# AC_board.net
KiCad netlist of a schematic drawn in Altium Designer
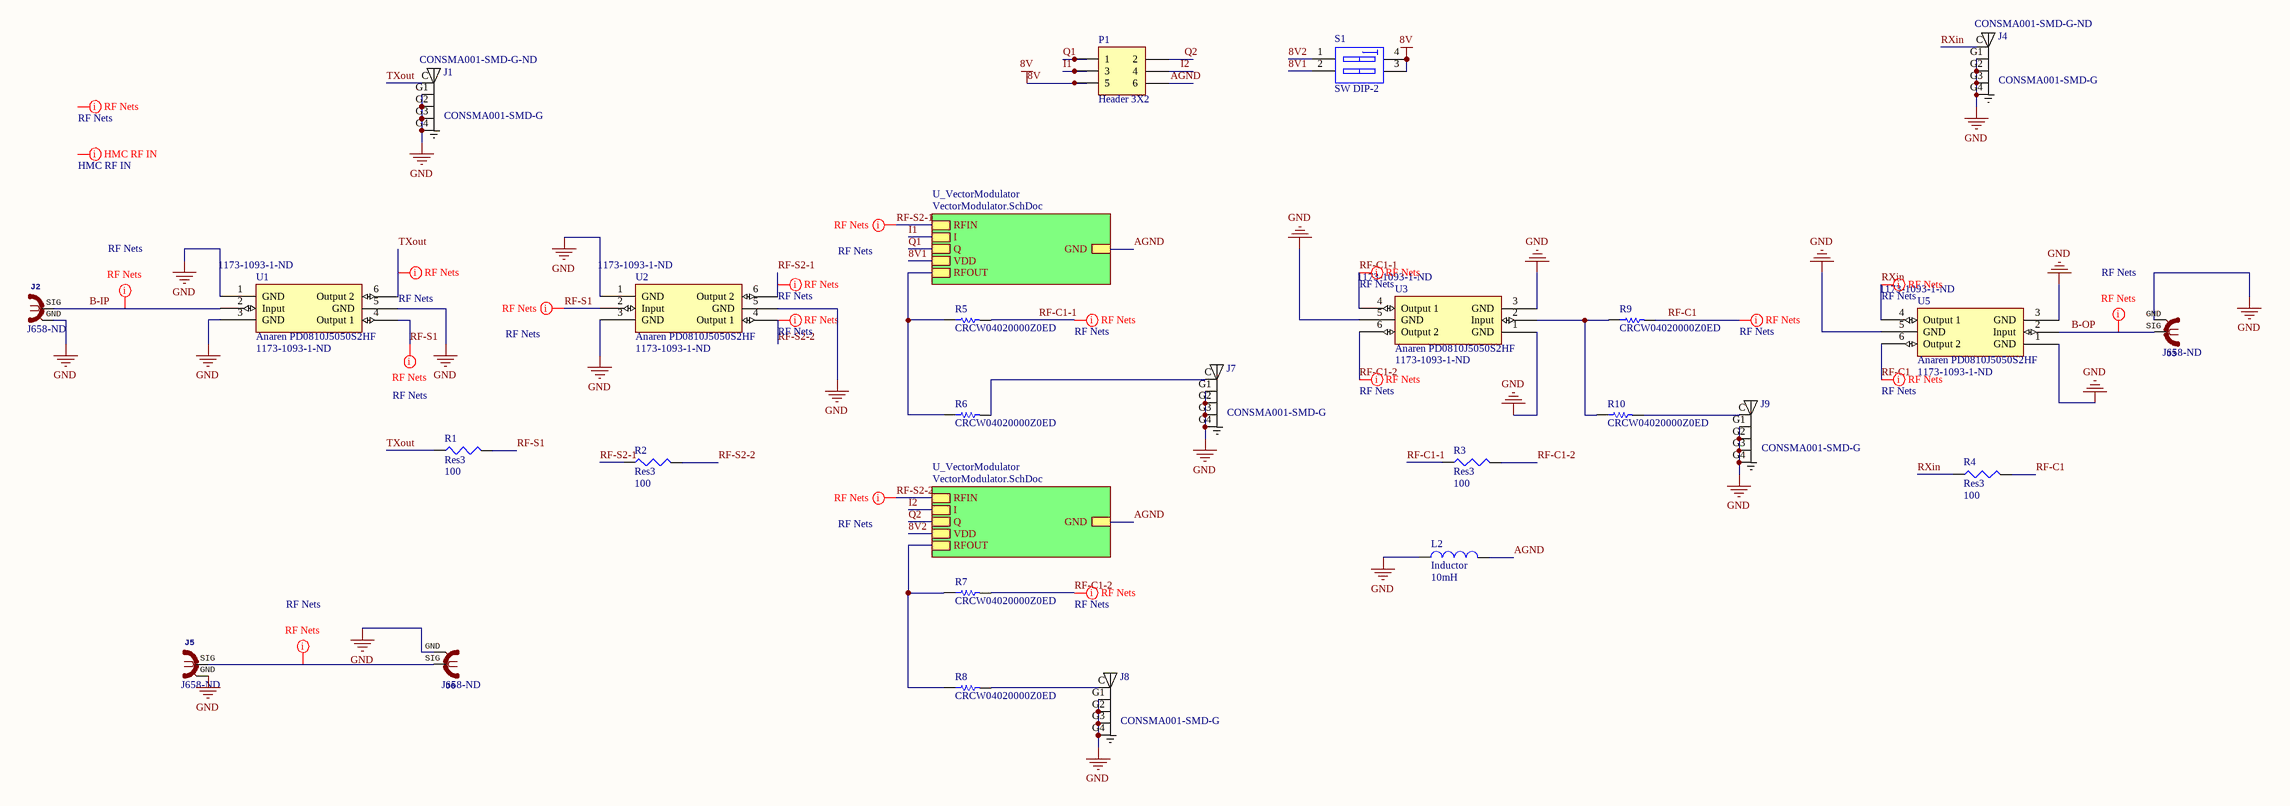
[diagram p0: AC_board.SchDoc]

(export (version "E")
  (design (tool "Eeschema 10.0.6"))
  (components
    (comp (ref "J1")
      (value "CONSMA001-SMD-G")
      (footprint "*LINX_CONSMA001-SMD-G_CONSMA001-SMD-G(Primary)")
      (description "50 Ohm Gold Plated Female PCB Mount SMA Connector")
      (fields
        (field (name "DIGI-KEY_PART_NUMBER") "CONSMA001-SMD-G-ND")
        (field (name "MF") "Linx Technologies")
        (field (name "SUPPLIER PART NUMBER 1") "CONSMA001-SMD-G-ND")
      )
      (libsource (lib "CONSMA001-SMD-G") (part "CONSMA001-SMD-G"))
    )
    (comp (ref "J2")
      (value "SMA 50 Ohm edge")
      (footprint "SMA-OSHPARK-4L-1.6MM- ALT3")
      (fields
        (field (name "SUPPLIER PART NUMBER 1") "J658-ND")
        (field (name "LIBRARYNAME") "dword1511-connectors")
      )
      (libsource (lib "wcsng_altium") (part "SMA-OSHPARK-4L-1.6MM-ALT3"))
    )
    (comp (ref "J3")
      (value "SMA 50 Ohm edge")
      (footprint "SMA-OSHPARK-4L-1.6MM- ALT3")
      (fields
        (field (name "SUPPLIER PART NUMBER 1") "J658-ND")
        (field (name "LIBRARYNAME") "dword1511-connectors")
      )
      (libsource (lib "wcsng_altium") (part "SMA-OSHPARK-4L-1.6MM-ALT3"))
    )
    (comp (ref "J4")
      (value "CONSMA001-SMD-G")
      (footprint "*LINX_CONSMA001-SMD-G_CONSMA001-SMD-G(Primary)")
      (description "50 Ohm Gold Plated Female PCB Mount SMA Connector")
      (fields
        (field (name "DIGI-KEY_PART_NUMBER") "CONSMA001-SMD-G-ND")
        (field (name "MF") "Linx Technologies")
        (field (name "SUPPLIER PART NUMBER 1") "CONSMA001-SMD-G-ND")
      )
      (libsource (lib "CONSMA001-SMD-G") (part "CONSMA001-SMD-G"))
    )
    (comp (ref "J5")
      (value "SMA 50 Ohm edge")
      (footprint "SMA-OSHPARK-4L-1.6MM- ALT3")
      (fields
        (field (name "SUPPLIER PART NUMBER 1") "J658-ND")
        (field (name "LIBRARYNAME") "dword1511-connectors")
      )
      (libsource (lib "wcsng_altium") (part "SMA-OSHPARK-4L-1.6MM-ALT3"))
    )
    (comp (ref "J6")
      (value "SMA 50 Ohm edge")
      (footprint "SMA-OSHPARK-4L-1.6MM- ALT3")
      (fields
        (field (name "SUPPLIER PART NUMBER 1") "J658-ND")
        (field (name "LIBRARYNAME") "dword1511-connectors")
      )
      (libsource (lib "wcsng_altium") (part "SMA-OSHPARK-4L-1.6MM-ALT3"))
    )
    (comp (ref "J7")
      (value "CONSMA001-SMD-G")
      (footprint "*LINX_CONSMA001-SMD-G_CONSMA001-SMD-G(Primary)")
      (description "50 Ohm Gold Plated Female PCB Mount SMA Connector")
      (fields
        (field (name "DIGI-KEY_PART_NUMBER") "CONSMA001-SMD-G-ND")
        (field (name "MF") "Linx Technologies")
      )
      (libsource (lib "CONSMA001-SMD-G") (part "CONSMA001-SMD-G"))
    )
    (comp (ref "J8")
      (value "CONSMA001-SMD-G")
      (footprint "*LINX_CONSMA001-SMD-G_CONSMA001-SMD-G(Primary)")
      (description "50 Ohm Gold Plated Female PCB Mount SMA Connector")
      (fields
        (field (name "DIGI-KEY_PART_NUMBER") "CONSMA001-SMD-G-ND")
        (field (name "MF") "Linx Technologies")
      )
      (libsource (lib "CONSMA001-SMD-G") (part "CONSMA001-SMD-G"))
    )
    (comp (ref "J9")
      (value "CONSMA001-SMD-G")
      (footprint "*LINX_CONSMA001-SMD-G_CONSMA001-SMD-G(Primary)")
      (description "50 Ohm Gold Plated Female PCB Mount SMA Connector")
      (fields
        (field (name "DIGI-KEY_PART_NUMBER") "CONSMA001-SMD-G-ND")
        (field (name "MF") "Linx Technologies")
      )
      (libsource (lib "CONSMA001-SMD-G") (part "CONSMA001-SMD-G"))
    )
    (comp (ref "L2")
      (value "Inductor")
      (footprint "0402-A")
      (fields (field (name "ALTIUM_VALUE") "10mH") (field (name "PUBLISHER") "Altium Limited"))
      (libsource (lib "Miscellaneous Devices") (part "Inductor"))
    )
    (comp (ref "P1")
      (value "Header 3X2")
      (footprint "HDR2X3")
      (description "Header, 3-Pin, Dual row")
      (fields (field (name "PUBLISHER") "Altium Limited"))
      (libsource (lib "Miscellaneous Connectors") (part "Header 3X2"))
    )
    (comp (ref "R1")
      (value "Res3")
      (footprint "J1-0603")
      (description "Resistor")
      (fields (field (name "ALTIUM_VALUE") "100") (field (name "PUBLISHER") "Altium Limited"))
      (libsource (lib "Miscellaneous Devices") (part "Res3"))
    )
    (comp (ref "R2")
      (value "Res3")
      (footprint "J1-0603")
      (description "Resistor")
      (fields (field (name "ALTIUM_VALUE") "100") (field (name "PUBLISHER") "Altium Limited"))
      (libsource (lib "Miscellaneous Devices") (part "Res3"))
    )
    (comp (ref "R3")
      (value "Res3")
      (footprint "J1-0603")
      (description "Resistor")
      (fields (field (name "ALTIUM_VALUE") "100") (field (name "PUBLISHER") "Altium Limited"))
      (libsource (lib "Miscellaneous Devices") (part "Res3"))
    )
    (comp (ref "R4")
      (value "Res3")
      (footprint "J1-0603")
      (description "Resistor")
      (fields (field (name "ALTIUM_VALUE") "100") (field (name "PUBLISHER") "Altium Limited"))
      (libsource (lib "Miscellaneous Devices") (part "Res3"))
    )
    (comp (ref "R5")
      (value "CRCW04020000Z0ED")
      (footprint "RESC1005X40X25ML05T05")
      (fields (field (name "MANUFACTURER") "Vishay Dale"))
      (libsource (lib "Altium Content Vault") (part "RES"))
    )
    (comp (ref "R6")
      (value "CRCW04020000Z0ED")
      (footprint "RESC1005X40X25ML05T05")
      (fields (field (name "MANUFACTURER") "Vishay Dale"))
      (libsource (lib "Altium Content Vault") (part "RES"))
    )
    (comp (ref "R7")
      (value "CRCW04020000Z0ED")
      (footprint "RESC1005X40X25ML05T05")
      (fields (field (name "MANUFACTURER") "Vishay Dale"))
      (libsource (lib "Altium Content Vault") (part "RES"))
    )
    (comp (ref "R8")
      (value "CRCW04020000Z0ED")
      (footprint "RESC1005X40X25ML05T05")
      (fields (field (name "MANUFACTURER") "Vishay Dale"))
      (libsource (lib "Altium Content Vault") (part "RES"))
    )
    (comp (ref "R9")
      (value "CRCW04020000Z0ED")
      (footprint "RESC1005X40X25ML05T05")
      (fields (field (name "MANUFACTURER") "Vishay Dale"))
      (libsource (lib "Altium Content Vault") (part "RES"))
    )
    (comp (ref "R10")
      (value "CRCW04020000Z0ED")
      (footprint "RESC1005X40X25ML05T05")
      (fields (field (name "MANUFACTURER") "Vishay Dale"))
      (libsource (lib "Altium Content Vault") (part "RES"))
    )
    (comp (ref "S1")
      (value "SW DIP-2")
      (footprint "DIP-4")
      (description "DIP Switch, 2 Position, SPST")
      (fields (field (name "PUBLISHER") "Altium Limited"))
      (libsource (lib "Miscellaneous Devices") (part "SW DIP-2"))
    )
    (comp (ref "U1")
      (value "Anaren PD0810J5050S2HF")
      (footprint "*ANAREN_PD0409J7575S2HF")
      (fields (field (name "U*") "1173-1093-1-ND") (field (name "SUPPLIER PART NUMBER 1") "1173-1093-1-ND"))
      (libsource (lib "") (part "Anaren PD0810J5050S2HF_1"))
    )
    (comp (ref "U2")
      (value "Anaren PD0810J5050S2HF")
      (footprint "*ANAREN_PD0409J7575S2HF")
      (fields (field (name "U*") "1173-1093-1-ND") (field (name "SUPPLIER PART NUMBER 1") "1173-1093-1-ND"))
      (libsource (lib "") (part "Anaren PD0810J5050S2HF_1"))
    )
    (comp (ref "U3")
      (value "Anaren PD0810J5050S2HF")
      (footprint "*ANAREN_PD0409J7575S2HF")
      (fields (field (name "U*") "1173-1093-1-ND") (field (name "SUPPLIER PART NUMBER 1") "1173-1093-1-ND"))
      (libsource (lib "wcsng_altium") (part "Anaren PD0810J5050S2HF"))
    )
    (comp (ref "U5")
      (value "Anaren PD0810J5050S2HF")
      (footprint "*ANAREN_PD0409J7575S2HF")
      (fields (field (name "U*") "1173-1093-1-ND") (field (name "SUPPLIER PART NUMBER 1") "1173-1093-1-ND"))
      (libsource (lib "wcsng_altium") (part "Anaren PD0810J5050S2HF"))
    )
  )
  (nets
    (net (code "1") (name "/8V1") (class "Default")
      (node (ref "S1") (pin "2") (pinfunction "A2_2") (pintype "passive"))
    )
    (net (code "2") (name "/8V2") (class "Default")
      (node (ref "S1") (pin "1") (pinfunction "A1_1") (pintype "passive"))
    )
    (net (code "3") (name "/AGND") (class "Default")
      (node (ref "L2") (pin "2") (pinfunction "2_2") (pintype "passive"))
      (node (ref "P1") (pin "6") (pinfunction "6_6") (pintype "passive"))
    )
    (net (code "4") (name "/B-IP") (class "Default")
      (node (ref "J2") (pin "SIG") (pinfunction "SIG_SIG") (pintype "passive"))
      (node (ref "U1") (pin "2") (pinfunction "Input_2") (pintype "bidirectional"))
    )
    (net (code "5") (name "/B-OP") (class "Default")
      (node (ref "J3") (pin "SIG") (pinfunction "SIG_SIG") (pintype "passive"))
      (node (ref "U5") (pin "2") (pinfunction "Input_2") (pintype "bidirectional"))
    )
    (net (code "6") (name "/I1") (class "Default")
      (node (ref "P1") (pin "3") (pinfunction "3_3") (pintype "passive"))
    )
    (net (code "7") (name "/I2") (class "Default")
      (node (ref "P1") (pin "4") (pinfunction "4_4") (pintype "passive"))
    )
    (net (code "8") (name "/Q1") (class "Default")
      (node (ref "P1") (pin "1") (pinfunction "1_1") (pintype "passive"))
    )
    (net (code "9") (name "/Q2") (class "Default")
      (node (ref "P1") (pin "2") (pinfunction "2_2") (pintype "passive"))
    )
    (net (code "10") (name "/RF-C1") (class "Default")
      (node (ref "R4") (pin "2") (pinfunction "2_2") (pintype "passive"))
      (node (ref "R9") (pin "2") (pinfunction "2_2") (pintype "passive"))
      (node (ref "U5") (pin "6") (pinfunction "Output_2_6") (pintype "bidirectional"))
    )
    (net (code "11") (name "/RF-C1-1") (class "Default")
      (node (ref "R3") (pin "1") (pinfunction "1_1") (pintype "passive"))
      (node (ref "R5") (pin "2") (pinfunction "2_2") (pintype "passive"))
      (node (ref "U3") (pin "4") (pinfunction "Output_1_4") (pintype "bidirectional"))
    )
    (net (code "12") (name "/RF-C1-2") (class "Default")
      (node (ref "R3") (pin "2") (pinfunction "2_2") (pintype "passive"))
      (node (ref "R7") (pin "2") (pinfunction "2_2") (pintype "passive"))
      (node (ref "U3") (pin "6") (pinfunction "Output_2_6") (pintype "bidirectional"))
    )
    (net (code "13") (name "/RF-S1") (class "Default")
      (node (ref "R1") (pin "2") (pinfunction "2_2") (pintype "passive"))
      (node (ref "U1") (pin "4") (pinfunction "Output_1_4") (pintype "bidirectional"))
      (node (ref "U2") (pin "2") (pinfunction "Input_2") (pintype "bidirectional"))
    )
    (net (code "14") (name "/RF-S2-1") (class "Default")
      (node (ref "R2") (pin "1") (pinfunction "1_1") (pintype "passive"))
      (node (ref "U2") (pin "6") (pinfunction "Output_2_6") (pintype "bidirectional"))
    )
    (net (code "15") (name "/RF-S2-2") (class "Default")
      (node (ref "R2") (pin "2") (pinfunction "2_2") (pintype "passive"))
      (node (ref "U2") (pin "4") (pinfunction "Output_1_4") (pintype "bidirectional"))
    )
    (net (code "16") (name "/RFOUT") (class "Default")
      (node (ref "R7") (pin "1") (pinfunction "1_1") (pintype "passive"))
      (node (ref "R8") (pin "1") (pinfunction "1_1") (pintype "passive"))
    )
    (net (code "17") (name "/RFOUT_1") (class "Default")
      (node (ref "R5") (pin "1") (pinfunction "1_1") (pintype "passive"))
      (node (ref "R6") (pin "1") (pinfunction "1_1") (pintype "passive"))
    )
    (net (code "18") (name "/RXin") (class "Default")
      (node (ref "J4") (pin "C") (pinfunction "FEEDING_C") (pintype "passive"))
      (node (ref "R4") (pin "1") (pinfunction "1_1") (pintype "passive"))
      (node (ref "U5") (pin "4") (pinfunction "Output_1_4") (pintype "bidirectional"))
    )
    (net (code "19") (name "/TXout") (class "Default")
      (node (ref "J1") (pin "C") (pinfunction "FEEDING_C") (pintype "passive"))
      (node (ref "R1") (pin "1") (pinfunction "1_1") (pintype "passive"))
      (node (ref "U1") (pin "6") (pinfunction "Output_2_6") (pintype "bidirectional"))
    )
    (net (code "20") (name "8V") (class "Default")
      (node (ref "P1") (pin "5") (pinfunction "5_5") (pintype "passive"))
      (node (ref "S1") (pin "3") (pinfunction "B2_3") (pintype "passive"))
      (node (ref "S1") (pin "4") (pinfunction "B1_4") (pintype "passive"))
    )
    (net (code "21") (name "GND") (class "Default")
      (node (ref "J1") (pin "G1") (pinfunction "GND_G1") (pintype "power_in"))
      (node (ref "J1") (pin "G2") (pinfunction "GND_G2") (pintype "power_in"))
      (node (ref "J1") (pin "G3") (pinfunction "GND_G3") (pintype "power_in"))
      (node (ref "J1") (pin "G4") (pinfunction "GND_G4") (pintype "power_in"))
      (node (ref "J2") (pin "GND") (pinfunction "GND_GND") (pintype "passive"))
      (node (ref "J3") (pin "GND") (pinfunction "GND_GND") (pintype "passive"))
      (node (ref "J4") (pin "G1") (pinfunction "GND_G1") (pintype "power_in"))
      (node (ref "J4") (pin "G2") (pinfunction "GND_G2") (pintype "power_in"))
      (node (ref "J4") (pin "G3") (pinfunction "GND_G3") (pintype "power_in"))
      (node (ref "J4") (pin "G4") (pinfunction "GND_G4") (pintype "power_in"))
      (node (ref "J5") (pin "GND") (pinfunction "GND_GND") (pintype "passive"))
      (node (ref "J6") (pin "GND") (pinfunction "GND_GND") (pintype "passive"))
      (node (ref "J7") (pin "G1") (pinfunction "GND_G1") (pintype "power_in"))
      (node (ref "J7") (pin "G2") (pinfunction "GND_G2") (pintype "power_in"))
      (node (ref "J7") (pin "G3") (pinfunction "GND_G3") (pintype "power_in"))
      (node (ref "J7") (pin "G4") (pinfunction "GND_G4") (pintype "power_in"))
      (node (ref "J8") (pin "G1") (pinfunction "GND_G1") (pintype "power_in"))
      (node (ref "J8") (pin "G2") (pinfunction "GND_G2") (pintype "power_in"))
      (node (ref "J8") (pin "G3") (pinfunction "GND_G3") (pintype "power_in"))
      (node (ref "J8") (pin "G4") (pinfunction "GND_G4") (pintype "power_in"))
      (node (ref "J9") (pin "G1") (pinfunction "GND_G1") (pintype "power_in"))
      (node (ref "J9") (pin "G2") (pinfunction "GND_G2") (pintype "power_in"))
      (node (ref "J9") (pin "G3") (pinfunction "GND_G3") (pintype "power_in"))
      (node (ref "J9") (pin "G4") (pinfunction "GND_G4") (pintype "power_in"))
      (node (ref "L2") (pin "1") (pinfunction "1_1") (pintype "passive"))
      (node (ref "U1") (pin "1") (pinfunction "GND_1") (pintype "power_in"))
      (node (ref "U1") (pin "3") (pinfunction "GND_3") (pintype "power_in"))
      (node (ref "U1") (pin "5") (pinfunction "GND_5") (pintype "power_in"))
      (node (ref "U2") (pin "1") (pinfunction "GND_1") (pintype "power_in"))
      (node (ref "U2") (pin "3") (pinfunction "GND_3") (pintype "power_in"))
      (node (ref "U2") (pin "5") (pinfunction "GND_5") (pintype "power_in"))
      (node (ref "U3") (pin "1") (pinfunction "GND_1") (pintype "power_in"))
      (node (ref "U3") (pin "3") (pinfunction "GND_3") (pintype "power_in"))
      (node (ref "U3") (pin "5") (pinfunction "GND_5") (pintype "power_in"))
      (node (ref "U5") (pin "1") (pinfunction "GND_1") (pintype "power_in"))
      (node (ref "U5") (pin "3") (pinfunction "GND_3") (pintype "power_in"))
      (node (ref "U5") (pin "5") (pinfunction "GND_5") (pintype "power_in"))
    )
    (net (code "22") (name "Net-(J5-PadSIG)") (class "Default")
      (node (ref "J5") (pin "SIG") (pinfunction "SIG_SIG") (pintype "passive"))
      (node (ref "J6") (pin "SIG") (pinfunction "SIG_SIG") (pintype "passive"))
    )
    (net (code "23") (name "Net-(J7-FEEDING)") (class "Default")
      (node (ref "J7") (pin "C") (pinfunction "FEEDING_C") (pintype "passive"))
      (node (ref "R6") (pin "2") (pinfunction "2_2") (pintype "passive"))
    )
    (net (code "24") (name "Net-(J8-FEEDING)") (class "Default")
      (node (ref "J8") (pin "C") (pinfunction "FEEDING_C") (pintype "passive"))
      (node (ref "R8") (pin "2") (pinfunction "2_2") (pintype "passive"))
    )
    (net (code "25") (name "Net-(J9-FEEDING)") (class "Default")
      (node (ref "J9") (pin "C") (pinfunction "FEEDING_C") (pintype "passive"))
      (node (ref "R10") (pin "2") (pinfunction "2_2") (pintype "passive"))
    )
    (net (code "26") (name "Net-(U3-Input)") (class "Default")
      (node (ref "R10") (pin "1") (pinfunction "1_1") (pintype "passive"))
      (node (ref "R9") (pin "1") (pinfunction "1_1") (pintype "passive"))
      (node (ref "U3") (pin "2") (pinfunction "Input_2") (pintype "bidirectional"))
    )
  )
)
